# driverboard.net
KiCad netlist of a schematic drawn in EAGLE
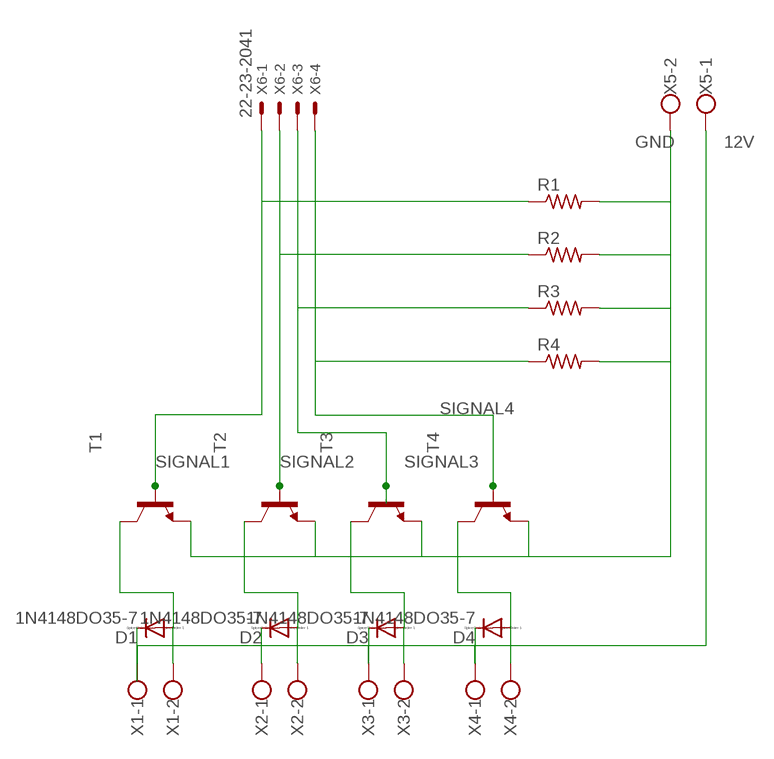
[diagram p0: schematic, sheet 1]

(export (version "E")
  (design (tool "Eeschema 10.0.6"))
  (components
    (comp (ref "D1")
      (value "1N4148DO35-7")
      (footprint "eagle-import:DO35-7")
      (libsource (lib "eagle-import") (part "1N4148DO35-7"))
    )
    (comp (ref "D2")
      (value "1N4148DO35-7")
      (footprint "eagle-import:DO35-7")
      (libsource (lib "eagle-import") (part "1N4148DO35-7"))
    )
    (comp (ref "D3")
      (value "1N4148DO35-7")
      (footprint "eagle-import:DO35-7")
      (libsource (lib "eagle-import") (part "1N4148DO35-7"))
    )
    (comp (ref "D4")
      (value "1N4148DO35-7")
      (footprint "eagle-import:DO35-7")
      (libsource (lib "eagle-import") (part "1N4148DO35-7"))
    )
    (comp (ref "R1")
      (value "R-US_0204/7")
      (footprint "eagle-import:0204_7")
      (libsource (lib "eagle-import") (part "R-US_0204/7"))
    )
    (comp (ref "R2")
      (value "R-US_0204/7")
      (footprint "eagle-import:0204_7")
      (libsource (lib "eagle-import") (part "R-US_0204/7"))
    )
    (comp (ref "R3")
      (value "R-US_0204/7")
      (footprint "eagle-import:0204_7")
      (libsource (lib "eagle-import") (part "R-US_0204/7"))
    )
    (comp (ref "R4")
      (value "R-US_0204/7")
      (footprint "eagle-import:0204_7")
      (libsource (lib "eagle-import") (part "R-US_0204/7"))
    )
    (comp (ref "T1")
      (value "BCV72-NPN-SOT23-BEC")
      (footprint "eagle-import:SOT23-BEC")
      (libsource (lib "eagle-import") (part "-NPN-SOT23-BECBCV72"))
    )
    (comp (ref "T2")
      (value "BCV72-NPN-SOT23-BEC")
      (footprint "eagle-import:SOT23-BEC")
      (libsource (lib "eagle-import") (part "-NPN-SOT23-BECBCV72"))
    )
    (comp (ref "T3")
      (value "BCV72-NPN-SOT23-BEC")
      (footprint "eagle-import:SOT23-BEC")
      (libsource (lib "eagle-import") (part "-NPN-SOT23-BECBCV72"))
    )
    (comp (ref "T4")
      (value "BCV72-NPN-SOT23-BEC")
      (footprint "eagle-import:SOT23-BEC")
      (libsource (lib "eagle-import") (part "-NPN-SOT23-BECBCV72"))
    )
    (comp (ref "X1")
      (value "W237-102")
      (footprint "eagle-import:W237-102")
      (fields (field (name "MPN") "237-102"))
      (libsource (lib "eagle-import") (part "W237-102"))
    )
    (comp (ref "X2")
      (value "W237-102")
      (footprint "eagle-import:W237-102")
      (fields (field (name "MPN") "237-102"))
      (libsource (lib "eagle-import") (part "W237-102"))
    )
    (comp (ref "X3")
      (value "W237-102")
      (footprint "eagle-import:W237-102")
      (fields (field (name "MPN") "237-102"))
      (libsource (lib "eagle-import") (part "W237-102"))
    )
    (comp (ref "X4")
      (value "W237-102")
      (footprint "eagle-import:W237-102")
      (fields (field (name "MPN") "237-102"))
      (libsource (lib "eagle-import") (part "W237-102"))
    )
    (comp (ref "X5")
      (value "W237-102")
      (footprint "eagle-import:W237-102")
      (fields (field (name "MPN") "237-102"))
      (libsource (lib "eagle-import") (part "W237-102"))
    )
    (comp (ref "X6")
      (value "22-23-2041")
      (footprint "eagle-import:22-23-2041")
      (fields (field (name "MF") "MOLEX"))
      (libsource (lib "eagle-import") (part "22-23-2041"))
    )
  )
  (nets
    (net (code "1") (name "/12V") (class "Default")
      (node (ref "D1") (pin "C") (pinfunction "C_C") (pintype "passive"))
      (node (ref "D2") (pin "C") (pinfunction "C_C") (pintype "passive"))
      (node (ref "D3") (pin "C") (pinfunction "C_C") (pintype "passive"))
      (node (ref "D4") (pin "C") (pinfunction "C_C") (pintype "passive"))
      (node (ref "X1") (pin "1") (pinfunction "KL_1") (pintype "passive"))
      (node (ref "X2") (pin "1") (pinfunction "KL_1") (pintype "passive"))
      (node (ref "X3") (pin "1") (pinfunction "KL_1") (pintype "passive"))
      (node (ref "X4") (pin "1") (pinfunction "KL_1") (pintype "passive"))
      (node (ref "X5") (pin "1") (pinfunction "KL_1") (pintype "passive"))
    )
    (net (code "2") (name "/GND") (class "Default")
      (node (ref "R1") (pin "2") (pinfunction "2_2") (pintype "passive"))
      (node (ref "R2") (pin "2") (pinfunction "2_2") (pintype "passive"))
      (node (ref "R3") (pin "2") (pinfunction "2_2") (pintype "passive"))
      (node (ref "R4") (pin "2") (pinfunction "2_2") (pintype "passive"))
      (node (ref "T1") (pin "E") (pinfunction "E_E") (pintype "passive"))
      (node (ref "T2") (pin "E") (pinfunction "E_E") (pintype "passive"))
      (node (ref "T3") (pin "E") (pinfunction "E_E") (pintype "passive"))
      (node (ref "T4") (pin "E") (pinfunction "E_E") (pintype "passive"))
      (node (ref "X5") (pin "2") (pinfunction "KL_2") (pintype "passive"))
    )
    (net (code "3") (name "/SIGNAL1") (class "Default")
      (node (ref "R1") (pin "1") (pinfunction "1_1") (pintype "passive"))
      (node (ref "T1") (pin "B") (pinfunction "B_B") (pintype "passive"))
      (node (ref "X6") (pin "1") (pinfunction "S_1") (pintype "passive"))
    )
    (net (code "4") (name "/SIGNAL2") (class "Default")
      (node (ref "R2") (pin "1") (pinfunction "1_1") (pintype "passive"))
      (node (ref "T2") (pin "B") (pinfunction "B_B") (pintype "passive"))
      (node (ref "X6") (pin "2") (pinfunction "S_2") (pintype "passive"))
    )
    (net (code "5") (name "/SIGNAL3") (class "Default")
      (node (ref "R3") (pin "1") (pinfunction "1_1") (pintype "passive"))
      (node (ref "T3") (pin "B") (pinfunction "B_B") (pintype "passive"))
      (node (ref "X6") (pin "3") (pinfunction "S_3") (pintype "passive"))
    )
    (net (code "6") (name "/SIGNAL4") (class "Default")
      (node (ref "R4") (pin "1") (pinfunction "1_1") (pintype "passive"))
      (node (ref "T4") (pin "B") (pinfunction "B_B") (pintype "passive"))
      (node (ref "X6") (pin "4") (pinfunction "S_4") (pintype "passive"))
    )
    (net (code "7") (name "Net-(X1B-KL)") (class "Default")
      (node (ref "D1") (pin "A") (pinfunction "A_A") (pintype "passive"))
      (node (ref "T1") (pin "C") (pinfunction "C_C") (pintype "passive"))
      (node (ref "X1") (pin "2") (pinfunction "KL_2") (pintype "passive"))
    )
    (net (code "8") (name "Net-(X2B-KL)") (class "Default")
      (node (ref "D2") (pin "A") (pinfunction "A_A") (pintype "passive"))
      (node (ref "T2") (pin "C") (pinfunction "C_C") (pintype "passive"))
      (node (ref "X2") (pin "2") (pinfunction "KL_2") (pintype "passive"))
    )
    (net (code "9") (name "Net-(X3B-KL)") (class "Default")
      (node (ref "D3") (pin "A") (pinfunction "A_A") (pintype "passive"))
      (node (ref "T3") (pin "C") (pinfunction "C_C") (pintype "passive"))
      (node (ref "X3") (pin "2") (pinfunction "KL_2") (pintype "passive"))
    )
    (net (code "10") (name "Net-(X4B-KL)") (class "Default")
      (node (ref "D4") (pin "A") (pinfunction "A_A") (pintype "passive"))
      (node (ref "T4") (pin "C") (pinfunction "C_C") (pintype "passive"))
      (node (ref "X4") (pin "2") (pinfunction "KL_2") (pintype "passive"))
    )
  )
)
